# FOTA_MicroController_Power_Trigger.net
KiCad netlist of a schematic drawn in Altium Designer
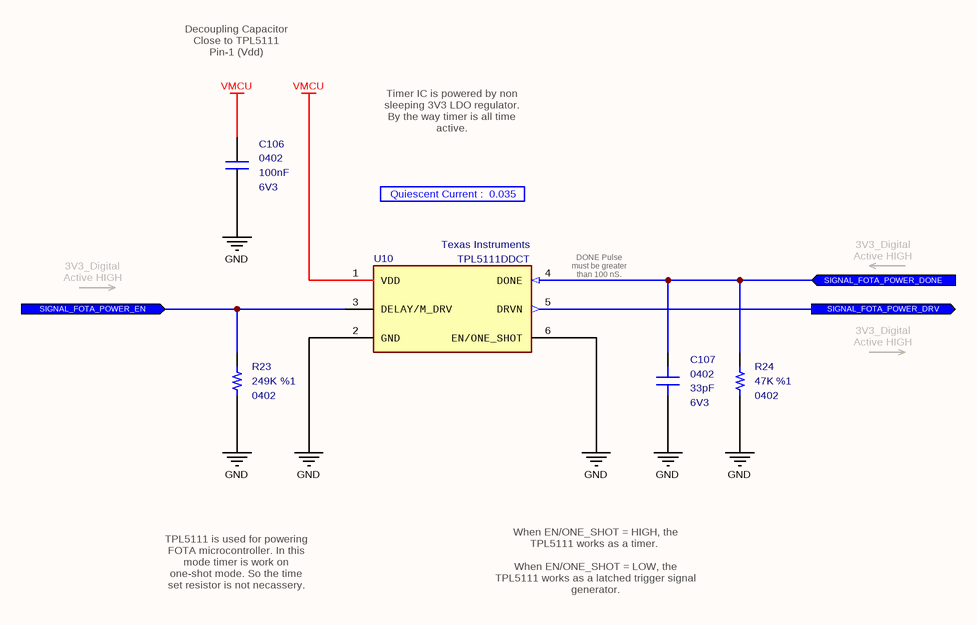
[diagram p0: FOTA MicroController Power Trigger.SchDoc]

(export (version "E")
  (design (tool "Eeschema 10.0.6"))
  (components
    (comp (ref "C106")
      (value "100nF")
      (footprint "CAPACITOR_0402")
      (description "Capacitor - 100nF [0402-6V3] (Ceramic)")
      (fields
        (field (name "MANUFACTURER_PART_NUMBER") "04026D104KAT4A")
        (field (name "MOUSER_PART_NUMBER") "581-04026D104KAT4A")
        (field (name "CASE") "0402")
        (field (name "VOLTAGE") "6V3")
      )
      (libsource (lib "Ovoo_Schematic") (part "Capacitor - 100nF [0402-6V3]"))
    )
    (comp (ref "C107")
      (value "33pF")
      (footprint "CAPACITOR_0402")
      (description "Capacitor - 33pF [0402] (Ceramic)")
      (fields
        (field (name "MANUFACTURER_PART_NUMBER") "C0402C330J9RACAUTO")
        (field (name "MOUSER_PART_NUMBER") "80-C0402C330J9RAUTO")
        (field (name "CASE") "0402")
        (field (name "VOLTAGE") "6V3")
      )
      (libsource (lib "Ovoo_Schematic") (part "Capacitor - 33pF [0402-6V3]"))
    )
    (comp (ref "R23")
      (value "249K")
      (footprint "RESISTOR_0402")
      (description "Thick Film Resistors - SMD 1/16 W 249 Kohms 1%")
      (fields
        (field (name "MANUFACTURER_PART_NUMBER") "CRCW0402249KFKED")
        (field (name "MOUSER_PART_NUMBER") "71-CRCW0402-249K-E3")
        (field (name "TOLERANCE") "%1")
        (field (name "CASE") "0402")
      )
      (libsource (lib "Ovoo_Schematic") (part "Resistor - 249K"))
    )
    (comp (ref "R24")
      (value "47K")
      (footprint "RESISTOR_0402")
      (description "Thick Film Resistors - SMD 1/16 W 47 Kohms 1%")
      (fields
        (field (name "MANUFACTURER_PART_NUMBER") "CRCW040247K0FKED")
        (field (name "MOUSER_PART_NUMBER") "71-CRCW0402-47K-E3")
        (field (name "TOLERANCE") "%1")
        (field (name "CASE") "0402")
      )
      (libsource (lib "Ovoo_Schematic") (part "Resistor - 47K"))
    )
    (comp (ref "U10")
      (value "Nanopower Timer IC")
      (footprint "SOT-23-6")
      (fields
        (field (name "MOUSER_PART_NUMBER") "595-TPL5111DDCT")
        (field (name "MANUFACTURER _PART_NUMBER") "TPL5111DDCT")
        (field (name "MANUFACTURER_NAME") "Texas Instruments")
      )
      (libsource (lib "Ovoo_Schematic") (part "IC - TPL5111"))
    )
  )
  (nets
    (net (code "1") (name "/SIGNAL_FOTA_POWER_DONE") (class "Default")
      (node (ref "C107") (pin "2") (pinfunction "2_2") (pintype "passive"))
      (node (ref "R24") (pin "2") (pinfunction "2_2") (pintype "passive"))
      (node (ref "U10") (pin "4") (pinfunction "DONE_4") (pintype "input"))
    )
    (net (code "2") (name "/SIGNAL_FOTA_POWER_DRV") (class "Default")
      (node (ref "U10") (pin "5") (pinfunction "DRVN_5") (pintype "output"))
    )
    (net (code "3") (name "/SIGNAL_FOTA_POWER_EN") (class "Default")
      (node (ref "R23") (pin "2") (pinfunction "2_2") (pintype "passive"))
      (node (ref "U10") (pin "3") (pinfunction "DELAY/M_DRV_3") (pintype "passive"))
    )
    (net (code "4") (name "GND") (class "Default")
      (node (ref "C106") (pin "1") (pinfunction "1_1") (pintype "passive"))
      (node (ref "C107") (pin "1") (pinfunction "1_1") (pintype "passive"))
      (node (ref "R23") (pin "1") (pinfunction "1_1") (pintype "passive"))
      (node (ref "R24") (pin "1") (pinfunction "1_1") (pintype "passive"))
      (node (ref "U10") (pin "2") (pinfunction "GND_2") (pintype "power_in"))
      (node (ref "U10") (pin "6") (pinfunction "EN/ONE_SHOT_6") (pintype "passive"))
    )
    (net (code "5") (name "VMCU") (class "Default")
      (node (ref "C106") (pin "2") (pinfunction "2_2") (pintype "passive"))
      (node (ref "U10") (pin "1") (pinfunction "VDD_1") (pintype "power_in"))
    )
  )
)
